# ActuatorSensor.net
KiCad netlist of a schematic drawn in Altium Designer
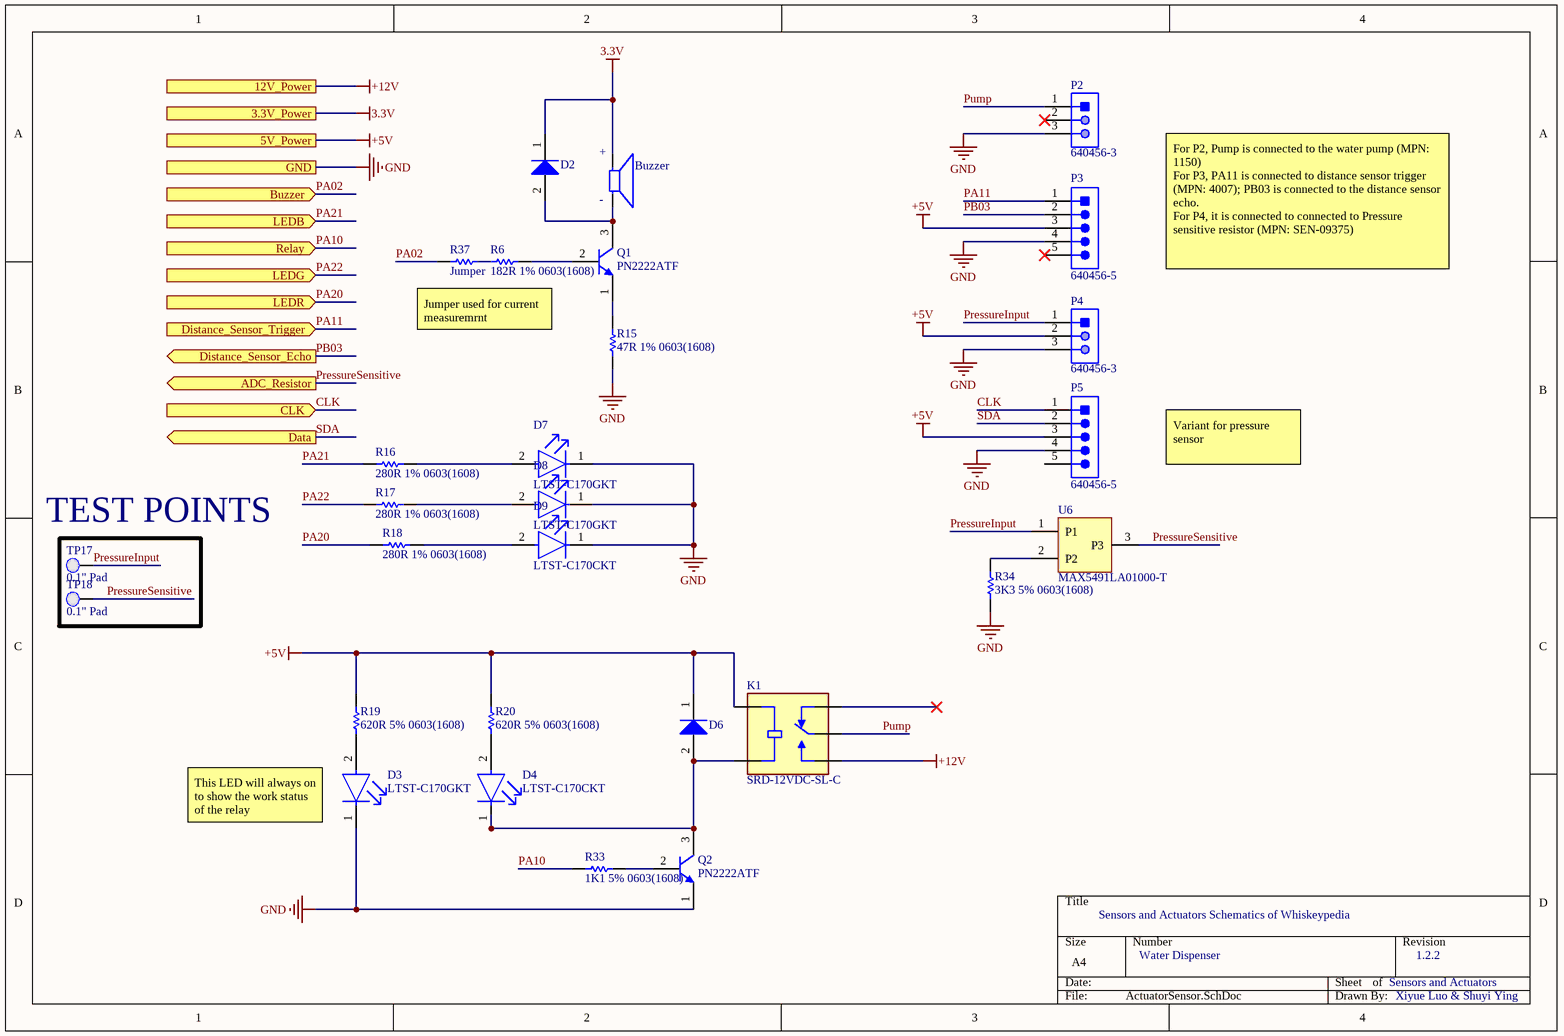
[diagram p0: ActuatorSensor.SchDoc]

(export (version "E")
  (design (tool "Eeschema 10.0.6"))
  (components
    (comp (ref "Buzzer")
      (value "Buzzer")
      (footprint "Buzzer")
      (description "8.5 mm, 5 Vo-p, 100 dB, Surface Mount (SMT), Magnetic Audio Transducer Buzzer")
      (fields
        (field (name "MANUFACTURER") "CUI Devices")
        (field (name "MANUFACTURER PART NUMBER") "CMT-8504-100-SMT-TR")
      )
      (libsource (lib "Whiskeypedia_Components") (part "Buzzer"))
    )
    (comp (ref "D2")
      (value "BAS16HT1G")
      (footprint "ONSC-SOD-323-2-477-02_V")
      (description "Switching Diode, 2-Pin SOD-323, Pb-Free, Tape and Reel")
      (fields (field (name "MANUFACTURER") "On Semiconductor"))
      (libsource (lib "Altium Content Vault") (part "ONSC-D-K1A2-2"))
    )
    (comp (ref "D3")
      (value "LTST-C170GKT")
      (footprint "FP-LTST-C170GKT-MFG")
      (description "LED GREEN CLEAR SMD")
      (fields (field (name "VOLTAGE") "5V"))
      (libsource (lib "Altium Content Vault") (part "8706943c75ba83719d021d2fdc84c58"))
    )
    (comp (ref "D4")
      (value "LTST-C170CKT")
      (footprint "FP-LTST-C170CKT-MFG")
      (description "LED RED CLEAR SMD")
      (fields (field (name "VOLTAGE") "5V"))
      (libsource (lib "Altium Content Vault") (part "8706943c75ba83719d021d2fdc84c58"))
    )
    (comp (ref "D6")
      (value "BAS16HT1G")
      (footprint "ONSC-SOD-323-2-477-02_V")
      (description "Switching Diode, 2-Pin SOD-323, Pb-Free, Tape and Reel")
      (fields (field (name "MANUFACTURER") "On Semiconductor"))
      (libsource (lib "Altium Content Vault") (part "ONSC-D-K1A2-2"))
    )
    (comp (ref "D7")
      (value "LTST-C170GKT")
      (footprint "FP-LTST-C170GKT-MFG")
      (description "LED GREEN CLEAR SMD")
      (fields (field (name "VOLTAGE") "5V"))
      (libsource (lib "Altium Content Vault") (part "8706943c75ba83719d021d2fdc84c58"))
    )
    (comp (ref "D8")
      (value "LTST-C170GKT")
      (footprint "FP-LTST-C170GKT-MFG")
      (description "LED GREEN CLEAR SMD")
      (fields (field (name "VOLTAGE") "5V"))
      (libsource (lib "Altium Content Vault") (part "8706943c75ba83719d021d2fdc84c58"))
    )
    (comp (ref "D9")
      (value "LTST-C170CKT")
      (footprint "FP-LTST-C170CKT-MFG")
      (description "LED RED CLEAR SMD")
      (fields (field (name "VOLTAGE") "5V"))
      (libsource (lib "Altium Content Vault") (part "8706943c75ba83719d021d2fdc84c58"))
    )
    (comp (ref "K1")
      (value "SRD-12VDC-SL-C")
      (footprint "RELAY_SRD-12VDC-SL-C")
      (description "General Purpose Non Latching 12VDC SPDT Through Hole Relays RoHS")
      (fields (field (name "MF") "Songle Relay"))
      (libsource (lib "Whiskeypedia_Components") (part "SRD-12VDC-SL-C"))
    )
    (comp (ref "P2")
      (value "640456-3")
      (footprint "TECO-640456-3")
      (description "Male Header, Pitch 2.54 mm, 1 x 3 Position, Height 10.03 mm, Tail Length 3.56 mm, -55 to 105 degC")
      (fields (field (name "MANUFACTURER") "TE Connectivity"))
      (libsource (lib "Altium Content Vault") (part "CN-1P-M-R3"))
    )
    (comp (ref "P3")
      (value "640456-5")
      (footprint "TECO-640456-5")
      (fields (field (name "MANUFACTURER") "TE Connectivity"))
      (libsource (lib "Altium Content Vault") (part "CN-1P-M-R5"))
    )
    (comp (ref "P4")
      (value "640456-3")
      (footprint "TECO-640456-3")
      (description "Male Header, Pitch 2.54 mm, 1 x 3 Position, Height 10.03 mm, Tail Length 3.56 mm, -55 to 105 degC")
      (fields (field (name "MANUFACTURER") "TE Connectivity"))
      (libsource (lib "Altium Content Vault") (part "CN-1P-M-R3"))
    )
    (comp (ref "P5")
      (value "640456-5")
      (footprint "TECO-640456-5")
      (fields (field (name "MANUFACTURER") "TE Connectivity"))
      (libsource (lib "Altium Content Vault") (part "CN-1P-M-R5"))
    )
    (comp (ref "Q1")
      (value "PN2222ATF")
      (footprint "FAIR-TO-92-3")
      (description "NPN General-Purpose Amplifier, 40 V, -55 to 150 degC, 3-Pin TO-92, RoHS, Tape and Reel")
      (fields (field (name "MANUFACTURER") "FairchildSemiconductor"))
      (libsource (lib "Altium Content Vault") (part "BJT-NPN-EBC-3"))
    )
    (comp (ref "Q2")
      (value "PN2222ATF")
      (footprint "FAIR-TO-92-3")
      (description "NPN General-Purpose Amplifier, 40 V, -55 to 150 degC, 3-Pin TO-92, RoHS, Tape and Reel")
      (fields (field (name "MANUFACTURER") "FairchildSemiconductor"))
      (libsource (lib "Altium Content Vault") (part "BJT-NPN-EBC-3"))
    )
    (comp (ref "R6")
      (value "182R 1% 0603(1608)")
      (footprint "RESC0603(1608)_N")
      (description "182R 0.1W 1% 0603 (1608 Metric)  SMD")
      (fields (field (name "TOLERANCE") "1 %") (field (name "POWER") "0.1 W"))
      (libsource (lib "Altium Content Vault") (part "RES"))
    )
    (comp (ref "R15")
      (value "47R 1% 0603(1608)")
      (footprint "RESC0603(1608)_M")
      (description "47R 0.1W 1% 0603 (1608 Metric)  SMD")
      (fields (field (name "POWER") "0.1 W") (field (name "TOLERANCE") "1 %"))
      (libsource (lib "Altium Content Vault") (part "RES"))
    )
    (comp (ref "R16")
      (value "280R 1% 0603(1608)")
      (footprint "RESC0603(1608)_M")
      (description "280R 0.1W 1% 0603 (1608 Metric)  SMD")
      (fields (field (name "POWER") "0.1 W") (field (name "TOLERANCE") "1 %"))
      (libsource (lib "Altium Content Vault") (part "RES"))
    )
    (comp (ref "R17")
      (value "280R 1% 0603(1608)")
      (footprint "RESC0603(1608)_M")
      (description "280R 0.1W 1% 0603 (1608 Metric)  SMD")
      (fields (field (name "POWER") "0.1 W") (field (name "TOLERANCE") "1 %"))
      (libsource (lib "Altium Content Vault") (part "RES"))
    )
    (comp (ref "R18")
      (value "280R 1% 0603(1608)")
      (footprint "RESC0603(1608)_M")
      (description "280R 0.1W 1% 0603 (1608 Metric)  SMD")
      (fields (field (name "POWER") "0.1 W") (field (name "TOLERANCE") "1 %"))
      (libsource (lib "Altium Content Vault") (part "RES"))
    )
    (comp (ref "R19")
      (value "620R 5% 0603(1608)")
      (footprint "RESC0603(1608)_M")
      (description "620R 0.1W 5% 0603 (1608 Metric)  SMD")
      (fields (field (name "TOLERANCE") "5 %") (field (name "POWER") "0.1 W"))
      (libsource (lib "Altium Content Vault") (part "RES"))
    )
    (comp (ref "R20")
      (value "620R 5% 0603(1608)")
      (footprint "RESC0603(1608)_M")
      (description "620R 0.1W 5% 0603 (1608 Metric)  SMD")
      (fields (field (name "TOLERANCE") "5 %") (field (name "POWER") "0.1 W"))
      (libsource (lib "Altium Content Vault") (part "RES"))
    )
    (comp (ref "R33")
      (value "1K1 5% 0603(1608)")
      (footprint "RESC0603(1608)_L")
      (description "1K1 0.1W 5% 0603 (1608 Metric)  SMD")
      (fields (field (name "POWER") "0.1 W") (field (name "TOLERANCE") "5 %"))
      (libsource (lib "Altium Content Vault") (part "RES"))
    )
    (comp (ref "R34")
      (value "3K3 5% 0603(1608)")
      (footprint "RESC0603(1608)_N")
      (description "3K3 0.1W 5% 0603 (1608 Metric)  SMD")
      (fields (field (name "TOLERANCE") "5 %") (field (name "POWER") "0.1 W"))
      (libsource (lib "Altium Content Vault") (part "RES"))
    )
    (comp (ref "R37")
      (value "Jumper")
      (footprint "RESC0805(2012)_N")
      (description "Jumper 0805 (2012 Metric)")
      (fields (field (name "TOLERANCE") "None"))
      (libsource (lib "Altium Content Vault") (part "RES"))
    )
    (comp (ref "TP17")
      (value "0.1\" Pad")
      (footprint "PCBComponent")
      (libsource (lib "Components - 12.02.20 - 18.05") (part "0.1{dblquote} Pad-A.4"))
    )
    (comp (ref "TP18")
      (value "0.1\" Pad")
      (footprint "PCBComponent")
      (libsource (lib "Components - 12.02.20 - 18.05") (part "0.1{dblquote} Pad-A.4"))
    )
    (comp (ref "U6")
      (value "MAX5491LA01000-T")
      (footprint "MAXM-U3-2_L")
      (description "30k 2 kV ESD Precision-Matched Resistor-Divider, -40 to 85 degC, 3-pin SOT (U3-2), Tape and Reel")
      (libsource (lib "Altium Content Vault") (part "MAX549X-U3X2"))
    )
  )
  (nets
    (net (code "1") (name "+5V") (class "Default")
      (node (ref "D6") (pin "1") (pinfunction "K_1") (pintype "passive"))
      (node (ref "K1") (pin "COIL1") (pinfunction "COIL1_COIL1") (pintype "passive"))
      (node (ref "P3") (pin "3") (pinfunction "TXO_3") (pintype "passive"))
      (node (ref "P4") (pin "2") (pinfunction "2_2") (pintype "passive"))
      (node (ref "P5") (pin "3") (pinfunction "TXO_3") (pintype "passive"))
      (node (ref "R19") (pin "2") (pinfunction "2_2") (pintype "passive"))
      (node (ref "R20") (pin "2") (pinfunction "2_2") (pintype "passive"))
    )
    (net (code "2") (name "+12V") (class "Default")
      (node (ref "K1") (pin "NO") (pinfunction "NO_NO") (pintype "passive"))
    )
    (net (code "3") (name "/CLK") (class "Default")
      (node (ref "P5") (pin "1") (pinfunction "DTR_1") (pintype "passive"))
    )
    (net (code "4") (name "/PA02") (class "Default")
      (node (ref "R37") (pin "1") (pinfunction "1_1") (pintype "passive"))
    )
    (net (code "5") (name "/PA10") (class "Default")
      (node (ref "R33") (pin "1") (pinfunction "1_1") (pintype "passive"))
    )
    (net (code "6") (name "/PA11") (class "Default")
      (node (ref "P3") (pin "1") (pinfunction "DTR_1") (pintype "passive"))
    )
    (net (code "7") (name "/PA20") (class "Default")
      (node (ref "R18") (pin "1") (pinfunction "1_1") (pintype "passive"))
    )
    (net (code "8") (name "/PA21") (class "Default")
      (node (ref "R16") (pin "1") (pinfunction "1_1") (pintype "passive"))
    )
    (net (code "9") (name "/PA22") (class "Default")
      (node (ref "R17") (pin "1") (pinfunction "1_1") (pintype "passive"))
    )
    (net (code "10") (name "/PB03") (class "Default")
      (node (ref "P3") (pin "2") (pinfunction "RXI_2") (pintype "passive"))
    )
    (net (code "11") (name "/PressureInput") (class "Default")
      (node (ref "P4") (pin "1") (pinfunction "1_1") (pintype "passive"))
      (node (ref "TP17") (pin "1") (pinfunction "PAD_1") (pintype "passive"))
      (node (ref "U6") (pin "1") (pinfunction "P1_1") (pintype "passive"))
    )
    (net (code "12") (name "/PressureSensitive") (class "Default")
      (node (ref "TP18") (pin "1") (pinfunction "PAD_1") (pintype "passive"))
      (node (ref "U6") (pin "3") (pinfunction "P3_3") (pintype "passive"))
    )
    (net (code "13") (name "/Pump") (class "Default")
      (node (ref "K1") (pin "COM") (pinfunction "COM_COM") (pintype "passive"))
      (node (ref "P2") (pin "1") (pinfunction "1_1") (pintype "passive"))
    )
    (net (code "14") (name "/SDA") (class "Default")
      (node (ref "P5") (pin "2") (pinfunction "RXI_2") (pintype "passive"))
    )
    (net (code "15") (name "3.3V") (class "Default")
      (node (ref "Buzzer") (pin "1") (pinfunction "1_1") (pintype "passive"))
      (node (ref "D2") (pin "1") (pinfunction "K_1") (pintype "passive"))
    )
    (net (code "16") (name "GND") (class "Default")
      (node (ref "D3") (pin "1") (pinfunction "C_1") (pintype "passive"))
      (node (ref "D7") (pin "1") (pinfunction "C_1") (pintype "passive"))
      (node (ref "D8") (pin "1") (pinfunction "C_1") (pintype "passive"))
      (node (ref "D9") (pin "1") (pinfunction "C_1") (pintype "passive"))
      (node (ref "P2") (pin "3") (pinfunction "3_3") (pintype "passive"))
      (node (ref "P3") (pin "4") (pinfunction "VCC_4") (pintype "passive"))
      (node (ref "P4") (pin "3") (pinfunction "3_3") (pintype "passive"))
      (node (ref "P5") (pin "4") (pinfunction "VCC_4") (pintype "passive"))
      (node (ref "Q2") (pin "1") (pinfunction "E_1") (pintype "passive"))
      (node (ref "R15") (pin "1") (pinfunction "1_1") (pintype "passive"))
      (node (ref "R34") (pin "1") (pinfunction "1_1") (pintype "passive"))
    )
    (net (code "17") (name "Net-(D2-A)") (class "Default")
      (node (ref "Buzzer") (pin "2") (pinfunction "2_2") (pintype "passive"))
      (node (ref "D2") (pin "2") (pinfunction "A_2") (pintype "passive"))
      (node (ref "Q1") (pin "3") (pinfunction "C_3") (pintype "passive"))
    )
    (net (code "18") (name "Net-(D3-A)") (class "Default")
      (node (ref "D3") (pin "2") (pinfunction "A_2") (pintype "passive"))
      (node (ref "R19") (pin "1") (pinfunction "1_1") (pintype "passive"))
    )
    (net (code "19") (name "Net-(D4-A)") (class "Default")
      (node (ref "D4") (pin "2") (pinfunction "A_2") (pintype "passive"))
      (node (ref "R20") (pin "1") (pinfunction "1_1") (pintype "passive"))
    )
    (net (code "20") (name "Net-(D4-C)") (class "Default")
      (node (ref "D4") (pin "1") (pinfunction "C_1") (pintype "passive"))
      (node (ref "D6") (pin "2") (pinfunction "A_2") (pintype "passive"))
      (node (ref "K1") (pin "COIL2") (pinfunction "COIL2_COIL2") (pintype "passive"))
      (node (ref "Q2") (pin "3") (pinfunction "C_3") (pintype "passive"))
    )
    (net (code "21") (name "Net-(D7-A)") (class "Default")
      (node (ref "D7") (pin "2") (pinfunction "A_2") (pintype "passive"))
      (node (ref "R16") (pin "2") (pinfunction "2_2") (pintype "passive"))
    )
    (net (code "22") (name "Net-(D8-A)") (class "Default")
      (node (ref "D8") (pin "2") (pinfunction "A_2") (pintype "passive"))
      (node (ref "R17") (pin "2") (pinfunction "2_2") (pintype "passive"))
    )
    (net (code "23") (name "Net-(D9-A)") (class "Default")
      (node (ref "D9") (pin "2") (pinfunction "A_2") (pintype "passive"))
      (node (ref "R18") (pin "2") (pinfunction "2_2") (pintype "passive"))
    )
    (net (code "24") (name "Net-(Q1-B)") (class "Default")
      (node (ref "Q1") (pin "2") (pinfunction "B_2") (pintype "passive"))
      (node (ref "R6") (pin "2") (pinfunction "2_2") (pintype "passive"))
    )
    (net (code "25") (name "Net-(Q1-E)") (class "Default")
      (node (ref "Q1") (pin "1") (pinfunction "E_1") (pintype "passive"))
      (node (ref "R15") (pin "2") (pinfunction "2_2") (pintype "passive"))
    )
    (net (code "26") (name "Net-(Q2-B)") (class "Default")
      (node (ref "Q2") (pin "2") (pinfunction "B_2") (pintype "passive"))
      (node (ref "R33") (pin "2") (pinfunction "2_2") (pintype "passive"))
    )
    (net (code "27") (name "Net-(R37-Pad2)") (class "Default")
      (node (ref "R37") (pin "2") (pinfunction "2_2") (pintype "passive"))
      (node (ref "R6") (pin "1") (pinfunction "1_1") (pintype "passive"))
    )
    (net (code "28") (name "Net-(U6-P2)") (class "Default")
      (node (ref "R34") (pin "2") (pinfunction "2_2") (pintype "passive"))
      (node (ref "U6") (pin "2") (pinfunction "P2_2") (pintype "passive"))
    )
    (net (code "29") (name "unconnected-(K1-PadNC)") (class "Default")
      (node (ref "K1") (pin "NC") (pinfunction "NC_NC") (pintype "passive+no_connect"))
    )
    (net (code "30") (name "unconnected-(P2-Pad2)") (class "Default")
      (node (ref "P2") (pin "2") (pinfunction "2_2") (pintype "passive+no_connect"))
    )
    (net (code "31") (name "unconnected-(P3-CTS-Pad5)") (class "Default")
      (node (ref "P3") (pin "5") (pinfunction "CTS_5") (pintype "passive+no_connect"))
    )
    (net (code "32") (name "unconnected-(P5-CTS-Pad5)") (class "Default")
      (node (ref "P5") (pin "5") (pinfunction "CTS_5") (pintype "passive"))
    )
  )
)
